# nfc-pn532-old.net
KiCad netlist of a schematic drawn in EAGLE
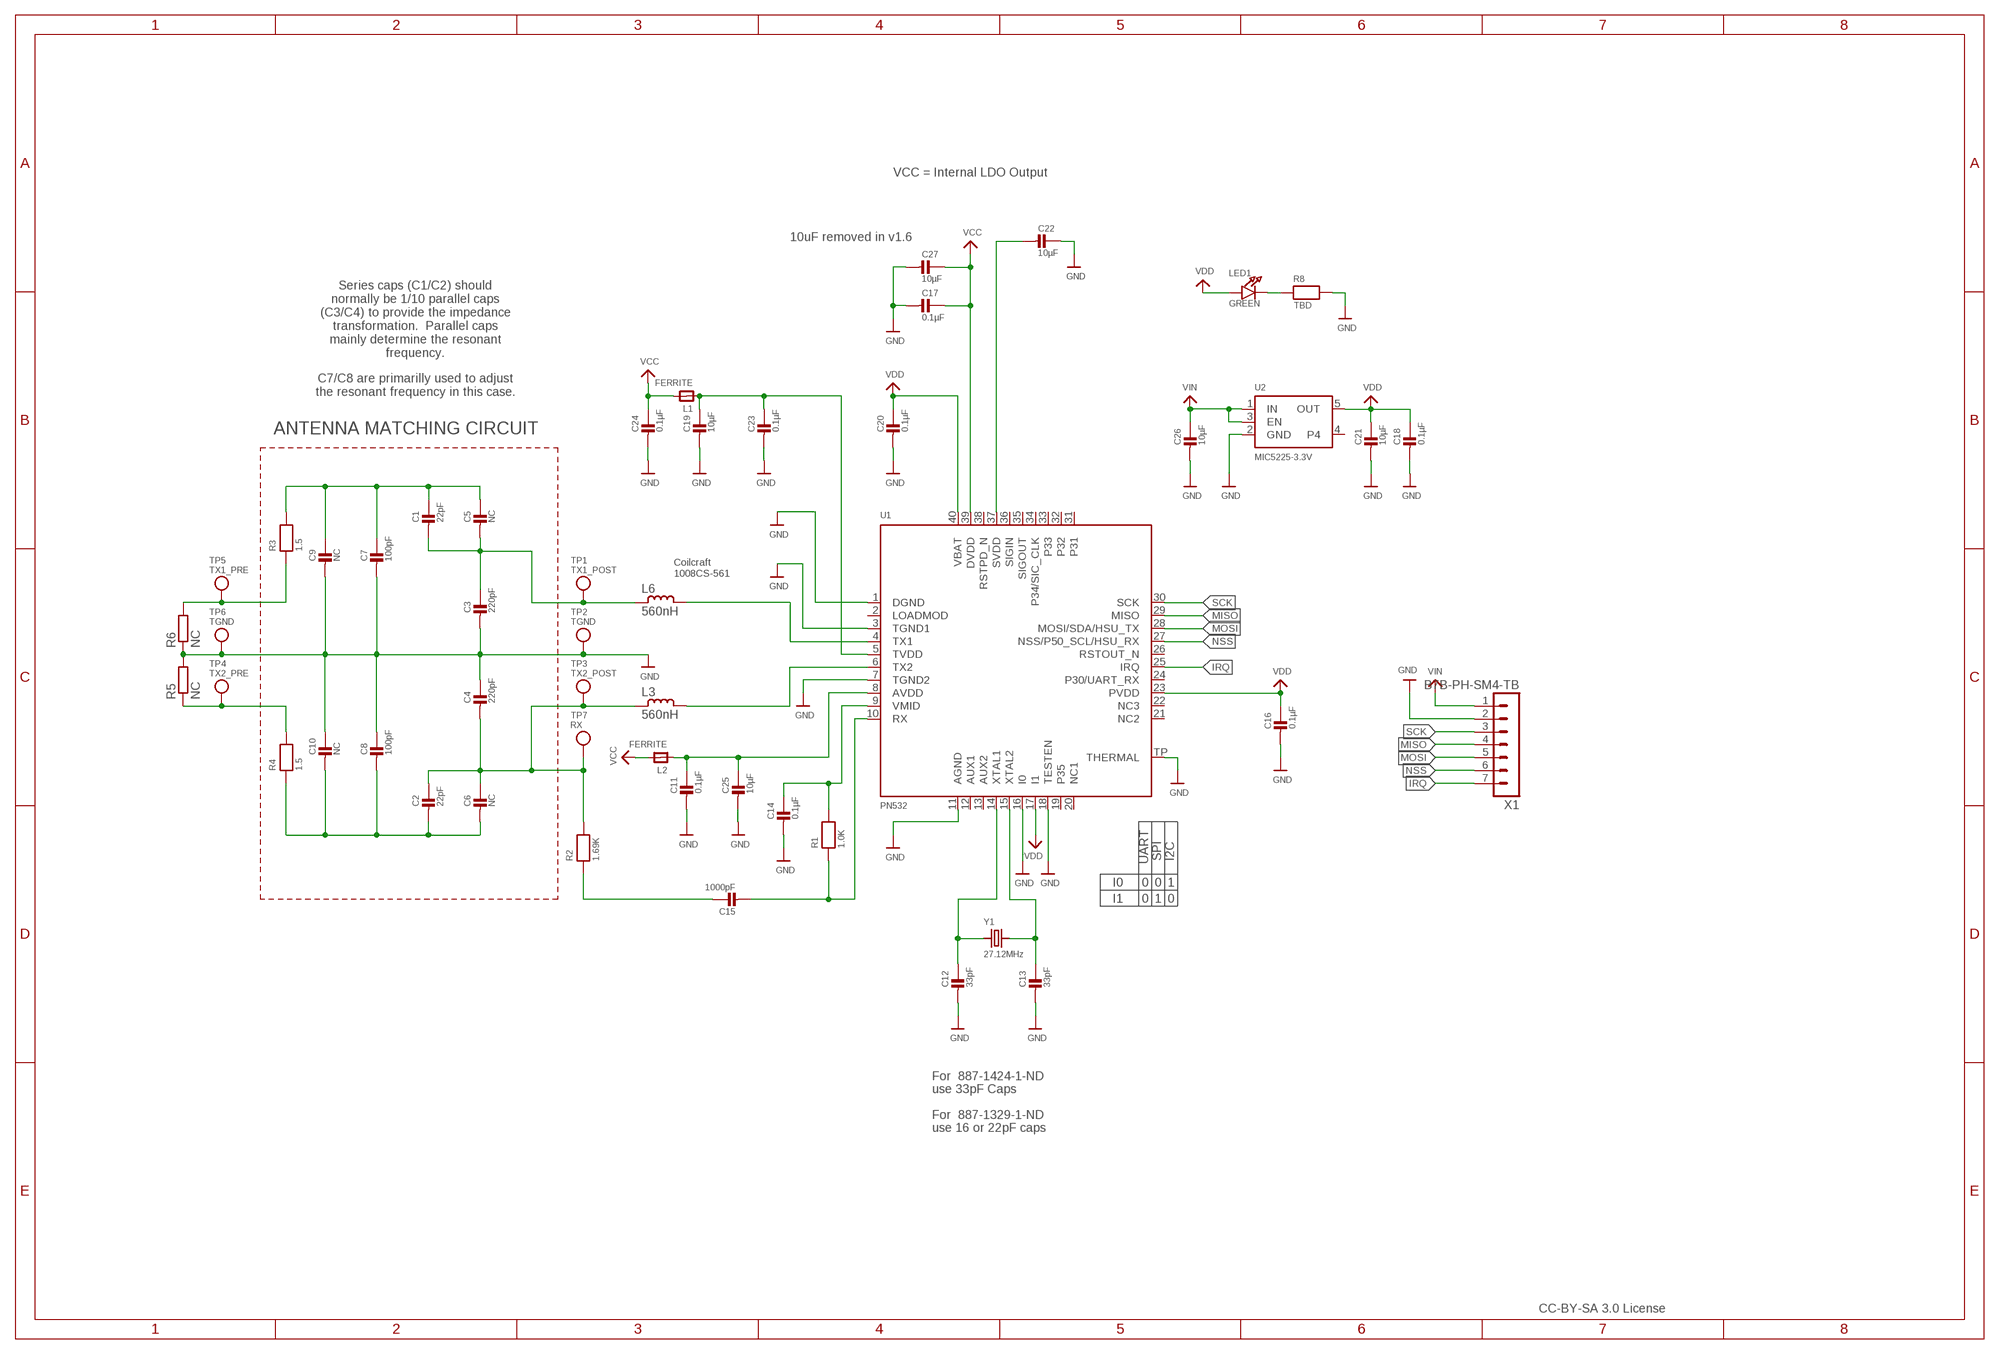
[diagram p0: schematic, sheet 1]

(export (version "E")
  (design (tool "Eeschema 10.0.6"))
  (components
    (comp (ref "C1")
      (value "22pF")
      (footprint "eagle-import:0805-NO")
      (libsource (lib "eagle-import") (part "CAP_CERAMIC0805-NOOUTLINE"))
    )
    (comp (ref "C2")
      (value "22pF")
      (footprint "eagle-import:0805-NO")
      (libsource (lib "eagle-import") (part "CAP_CERAMIC0805-NOOUTLINE"))
    )
    (comp (ref "C3")
      (value "220pF")
      (footprint "eagle-import:0805-NO")
      (libsource (lib "eagle-import") (part "CAP_CERAMIC0805-NOOUTLINE"))
    )
    (comp (ref "C4")
      (value "220pF")
      (footprint "eagle-import:0805-NO")
      (libsource (lib "eagle-import") (part "CAP_CERAMIC0805-NOOUTLINE"))
    )
    (comp (ref "C5")
      (value "NC")
      (footprint "eagle-import:0805-NO")
      (libsource (lib "eagle-import") (part "CAP_CERAMIC0805-NOOUTLINE"))
    )
    (comp (ref "C6")
      (value "NC")
      (footprint "eagle-import:0805-NO")
      (libsource (lib "eagle-import") (part "CAP_CERAMIC0805-NOOUTLINE"))
    )
    (comp (ref "C7")
      (value "100pF")
      (footprint "eagle-import:0805-NO")
      (libsource (lib "eagle-import") (part "CAP_CERAMIC0805-NOOUTLINE"))
    )
    (comp (ref "C8")
      (value "100pF")
      (footprint "eagle-import:0805-NO")
      (libsource (lib "eagle-import") (part "CAP_CERAMIC0805-NOOUTLINE"))
    )
    (comp (ref "C9")
      (value "NC")
      (footprint "eagle-import:0805-NO")
      (libsource (lib "eagle-import") (part "CAP_CERAMIC0805-NOOUTLINE"))
    )
    (comp (ref "C10")
      (value "NC")
      (footprint "eagle-import:0805-NO")
      (libsource (lib "eagle-import") (part "CAP_CERAMIC0805-NOOUTLINE"))
    )
    (comp (ref "C11")
      (value "0.1µF")
      (footprint "eagle-import:0805-NO")
      (libsource (lib "eagle-import") (part "CAP_CERAMIC0805-NOOUTLINE"))
    )
    (comp (ref "C12")
      (value "33pF")
      (footprint "eagle-import:0805-NO")
      (libsource (lib "eagle-import") (part "CAP_CERAMIC0805-NOOUTLINE"))
    )
    (comp (ref "C13")
      (value "33pF")
      (footprint "eagle-import:0805-NO")
      (libsource (lib "eagle-import") (part "CAP_CERAMIC0805-NOOUTLINE"))
    )
    (comp (ref "C14")
      (value "0.1µF")
      (footprint "eagle-import:0805-NO")
      (libsource (lib "eagle-import") (part "CAP_CERAMIC0805-NOOUTLINE"))
    )
    (comp (ref "C15")
      (value "1000pF")
      (footprint "eagle-import:0805-NO")
      (libsource (lib "eagle-import") (part "CAP_CERAMIC0805-NOOUTLINE"))
    )
    (comp (ref "C16")
      (value "0.1µF")
      (footprint "eagle-import:0805-NO")
      (libsource (lib "eagle-import") (part "CAP_CERAMIC0805-NOOUTLINE"))
    )
    (comp (ref "C17")
      (value "0.1µF")
      (footprint "eagle-import:0805-NO")
      (libsource (lib "eagle-import") (part "CAP_CERAMIC0805-NOOUTLINE"))
    )
    (comp (ref "C18")
      (value "0.1µF")
      (footprint "eagle-import:0805-NO")
      (libsource (lib "eagle-import") (part "CAP_CERAMIC0805-NOOUTLINE"))
    )
    (comp (ref "C19")
      (value "10µF")
      (footprint "eagle-import:0805-NO")
      (libsource (lib "eagle-import") (part "CAP_CERAMIC0805-NOOUTLINE"))
    )
    (comp (ref "C20")
      (value "0.1µF")
      (footprint "eagle-import:0805-NO")
      (libsource (lib "eagle-import") (part "CAP_CERAMIC0805-NOOUTLINE"))
    )
    (comp (ref "C21")
      (value "10µF")
      (footprint "eagle-import:0805-NO")
      (libsource (lib "eagle-import") (part "CAP_CERAMIC0805-NOOUTLINE"))
    )
    (comp (ref "C22")
      (value "10µF")
      (footprint "eagle-import:0805-NO")
      (libsource (lib "eagle-import") (part "CAP_CERAMIC0805-NOOUTLINE"))
    )
    (comp (ref "C23")
      (value "0.1µF")
      (footprint "eagle-import:0805-NO")
      (libsource (lib "eagle-import") (part "CAP_CERAMIC0805-NOOUTLINE"))
    )
    (comp (ref "C24")
      (value "0.1µF")
      (footprint "eagle-import:0805-NO")
      (libsource (lib "eagle-import") (part "CAP_CERAMIC0805-NOOUTLINE"))
    )
    (comp (ref "C25")
      (value "10µF")
      (footprint "eagle-import:0805-NO")
      (libsource (lib "eagle-import") (part "CAP_CERAMIC0805-NOOUTLINE"))
    )
    (comp (ref "C26")
      (value "10µF")
      (footprint "eagle-import:0805-NO")
      (libsource (lib "eagle-import") (part "CAP_CERAMIC0805-NOOUTLINE"))
    )
    (comp (ref "C27")
      (value "10µF")
      (footprint "eagle-import:0805-NO")
      (libsource (lib "eagle-import") (part "CAP_CERAMIC0805-NOOUTLINE"))
    )
    (comp (ref "L1")
      (value "FERRITE")
      (footprint "eagle-import:0805")
      (libsource (lib "eagle-import") (part "FERRITE0805"))
    )
    (comp (ref "L2")
      (value "FERRITE")
      (footprint "eagle-import:0805")
      (libsource (lib "eagle-import") (part "FERRITE0805"))
    )
    (comp (ref "L3")
      (value "560nH")
      (footprint "eagle-import:L1008CS")
      (libsource (lib "eagle-import") (part "L-1008CS"))
    )
    (comp (ref "L6")
      (value "560nH")
      (footprint "eagle-import:L1008CS")
      (libsource (lib "eagle-import") (part "L-1008CS"))
    )
    (comp (ref "LED1")
      (value "GREEN")
      (footprint "eagle-import:CHIPLED_0805_NOOUTLINE")
      (libsource (lib "eagle-import") (part "LED0805_NOOUTLINE"))
    )
    (comp (ref "R1")
      (value "1.0K")
      (footprint "eagle-import:0805-NO")
      (libsource (lib "eagle-import") (part "RESISTOR0805_NOOUTLINE"))
    )
    (comp (ref "R2")
      (value "1.69K")
      (footprint "eagle-import:0805-NO")
      (libsource (lib "eagle-import") (part "RESISTOR0805_NOOUTLINE"))
    )
    (comp (ref "R3")
      (value "1.5")
      (footprint "eagle-import:0805-NO")
      (libsource (lib "eagle-import") (part "RESISTOR0805_NOOUTLINE"))
    )
    (comp (ref "R4")
      (value "1.5")
      (footprint "eagle-import:0805-NO")
      (libsource (lib "eagle-import") (part "RESISTOR0805_NOOUTLINE"))
    )
    (comp (ref "R5")
      (value "NC")
      (footprint "eagle-import:R0201")
      (libsource (lib "eagle-import") (part "R-EU_R0201"))
    )
    (comp (ref "R6")
      (value "NC")
      (footprint "eagle-import:R0201")
      (libsource (lib "eagle-import") (part "R-EU_R0201"))
    )
    (comp (ref "R8")
      (value "TBD")
      (footprint "eagle-import:0805-NO")
      (libsource (lib "eagle-import") (part "RESISTOR0805_NOOUTLINE"))
    )
    (comp (ref "TP1")
      (value "TX1_POST")
      (footprint "eagle-import:TESTPOINT_ROUND_1MM")
      (libsource (lib "eagle-import") (part "TESTPOINTROUND1MM"))
    )
    (comp (ref "TP2")
      (value "TGND")
      (footprint "eagle-import:TESTPOINT_ROUND_1MM")
      (libsource (lib "eagle-import") (part "TESTPOINTROUND1MM"))
    )
    (comp (ref "TP3")
      (value "TX2_POST")
      (footprint "eagle-import:TESTPOINT_ROUND_1MM")
      (libsource (lib "eagle-import") (part "TESTPOINTROUND1MM"))
    )
    (comp (ref "TP4")
      (value "TX2_PRE")
      (footprint "eagle-import:TESTPOINT_ROUND_1MM")
      (libsource (lib "eagle-import") (part "TESTPOINTROUND1MM"))
    )
    (comp (ref "TP5")
      (value "TX1_PRE")
      (footprint "eagle-import:TESTPOINT_ROUND_1MM")
      (libsource (lib "eagle-import") (part "TESTPOINTROUND1MM"))
    )
    (comp (ref "TP6")
      (value "TGND")
      (footprint "eagle-import:TESTPOINT_ROUND_1MM")
      (libsource (lib "eagle-import") (part "TESTPOINTROUND1MM"))
    )
    (comp (ref "TP7")
      (value "RX")
      (footprint "eagle-import:TESTPOINT_ROUND_1MM")
      (libsource (lib "eagle-import") (part "TESTPOINTROUND1MM"))
    )
    (comp (ref "U1")
      (value "PN532")
      (footprint "eagle-import:HVQFN40-6X6")
      (libsource (lib "eagle-import") (part "PN532"))
    )
    (comp (ref "U2")
      (value "MIC5225-3.3V")
      (footprint "eagle-import:SOT23-5")
      (libsource (lib "eagle-import") (part "VREG_SOT23-5"))
    )
    (comp (ref "X1")
      (value "B7B-PH-SM4-TB")
      (footprint "eagle-import:B7B-PH-SM4-TB")
      (libsource (lib "eagle-import") (part "B7B-PH-SM4-TB"))
    )
    (comp (ref "Y1")
      (value "27.12MHz")
      (footprint "eagle-import:CRYSTAL_3.2X2.5")
      (libsource (lib "eagle-import") (part "CRYSTAL3.2X2.5"))
    )
  )
  (nets
    (net (code "1") (name "GND") (class "Default")
      (node (ref "C10") (pin "1") (pinfunction "1_1") (pintype "passive"))
      (node (ref "C11") (pin "2") (pinfunction "2_2") (pintype "passive"))
      (node (ref "C12") (pin "2") (pinfunction "2_2") (pintype "passive"))
      (node (ref "C13") (pin "2") (pinfunction "2_2") (pintype "passive"))
      (node (ref "C14") (pin "2") (pinfunction "2_2") (pintype "passive"))
      (node (ref "C16") (pin "2") (pinfunction "2_2") (pintype "passive"))
      (node (ref "C17") (pin "2") (pinfunction "2_2") (pintype "passive"))
      (node (ref "C18") (pin "2") (pinfunction "2_2") (pintype "passive"))
      (node (ref "C19") (pin "2") (pinfunction "2_2") (pintype "passive"))
      (node (ref "C20") (pin "2") (pinfunction "2_2") (pintype "passive"))
      (node (ref "C21") (pin "2") (pinfunction "2_2") (pintype "passive"))
      (node (ref "C22") (pin "1") (pinfunction "1_1") (pintype "passive"))
      (node (ref "C23") (pin "2") (pinfunction "2_2") (pintype "passive"))
      (node (ref "C24") (pin "2") (pinfunction "2_2") (pintype "passive"))
      (node (ref "C25") (pin "2") (pinfunction "2_2") (pintype "passive"))
      (node (ref "C26") (pin "2") (pinfunction "2_2") (pintype "passive"))
      (node (ref "C27") (pin "2") (pinfunction "2_2") (pintype "passive"))
      (node (ref "C3") (pin "2") (pinfunction "2_2") (pintype "passive"))
      (node (ref "C4") (pin "1") (pinfunction "1_1") (pintype "passive"))
      (node (ref "C7") (pin "2") (pinfunction "2_2") (pintype "passive"))
      (node (ref "C8") (pin "1") (pinfunction "1_1") (pintype "passive"))
      (node (ref "C9") (pin "2") (pinfunction "2_2") (pintype "passive"))
      (node (ref "R5") (pin "2") (pinfunction "2_2") (pintype "passive"))
      (node (ref "R6") (pin "1") (pinfunction "1_1") (pintype "passive"))
      (node (ref "R8") (pin "2") (pinfunction "2_2") (pintype "passive"))
      (node (ref "TP2") (pin "P$1") (pinfunction "P$1_P$1") (pintype "bidirectional"))
      (node (ref "TP6") (pin "P$1") (pinfunction "P$1_P$1") (pintype "bidirectional"))
      (node (ref "U1") (pin "1") (pinfunction "DGND_1") (pintype "bidirectional"))
      (node (ref "U1") (pin "11") (pinfunction "AGND_11") (pintype "bidirectional"))
      (node (ref "U1") (pin "16") (pinfunction "I0_16") (pintype "bidirectional"))
      (node (ref "U1") (pin "18") (pinfunction "TESTEN_18") (pintype "bidirectional"))
      (node (ref "U1") (pin "3") (pinfunction "TGND1_3") (pintype "bidirectional"))
      (node (ref "U1") (pin "7") (pinfunction "TGND2_7") (pintype "bidirectional"))
      (node (ref "U1") (pin "TP") (pinfunction "THERMAL_TP") (pintype "bidirectional"))
      (node (ref "U2") (pin "2") (pinfunction "GND_2") (pintype "power_in"))
      (node (ref "X1") (pin "2") (pinfunction "2_2") (pintype "passive"))
    )
    (net (code "2") (name "IRQ") (class "Default")
      (node (ref "U1") (pin "25") (pinfunction "IRQ_25") (pintype "bidirectional"))
      (node (ref "X1") (pin "7") (pinfunction "7_7") (pintype "passive"))
    )
    (net (code "3") (name "MISO") (class "Default")
      (node (ref "U1") (pin "29") (pinfunction "MISO_29") (pintype "bidirectional"))
      (node (ref "X1") (pin "4") (pinfunction "4_4") (pintype "passive"))
    )
    (net (code "4") (name "MOSI") (class "Default")
      (node (ref "U1") (pin "28") (pinfunction "MOSI/SDA/HSU_TX_28") (pintype "bidirectional"))
      (node (ref "X1") (pin "5") (pinfunction "5_5") (pintype "passive"))
    )
    (net (code "5") (name "NSS") (class "Default")
      (node (ref "U1") (pin "27") (pinfunction "NSS/P50_SCL/HSU_RX_27") (pintype "bidirectional"))
      (node (ref "X1") (pin "6") (pinfunction "6_6") (pintype "passive"))
    )
    (net (code "6") (name "Net-(C1-Pad1)") (class "Default")
      (node (ref "C1") (pin "1") (pinfunction "1_1") (pintype "passive"))
      (node (ref "C5") (pin "1") (pinfunction "1_1") (pintype "passive"))
      (node (ref "C7") (pin "1") (pinfunction "1_1") (pintype "passive"))
      (node (ref "C9") (pin "1") (pinfunction "1_1") (pintype "passive"))
      (node (ref "R3") (pin "2") (pinfunction "2_2") (pintype "passive"))
    )
    (net (code "7") (name "Net-(C10-Pad2)") (class "Default")
      (node (ref "C10") (pin "2") (pinfunction "2_2") (pintype "passive"))
      (node (ref "C2") (pin "2") (pinfunction "2_2") (pintype "passive"))
      (node (ref "C6") (pin "2") (pinfunction "2_2") (pintype "passive"))
      (node (ref "C8") (pin "2") (pinfunction "2_2") (pintype "passive"))
      (node (ref "R4") (pin "1") (pinfunction "1_1") (pintype "passive"))
    )
    (net (code "8") (name "Net-(C15-Pad1)") (class "Default")
      (node (ref "C15") (pin "1") (pinfunction "1_1") (pintype "passive"))
      (node (ref "R2") (pin "1") (pinfunction "1_1") (pintype "passive"))
    )
    (net (code "9") (name "Net-(L1-P$1)") (class "Default")
      (node (ref "C19") (pin "1") (pinfunction "1_1") (pintype "passive"))
      (node (ref "C23") (pin "1") (pinfunction "1_1") (pintype "passive"))
      (node (ref "L1") (pin "1") (pinfunction "P$1_1") (pintype "passive"))
      (node (ref "U1") (pin "5") (pinfunction "TVDD_5") (pintype "bidirectional"))
    )
    (net (code "10") (name "Net-(L2-P$1)") (class "Default")
      (node (ref "C11") (pin "1") (pinfunction "1_1") (pintype "passive"))
      (node (ref "C25") (pin "1") (pinfunction "1_1") (pintype "passive"))
      (node (ref "L2") (pin "1") (pinfunction "P$1_1") (pintype "passive"))
      (node (ref "U1") (pin "8") (pinfunction "AVDD_8") (pintype "bidirectional"))
    )
    (net (code "11") (name "Net-(L3-P$1)") (class "Default")
      (node (ref "C2") (pin "1") (pinfunction "1_1") (pintype "passive"))
      (node (ref "C4") (pin "2") (pinfunction "2_2") (pintype "passive"))
      (node (ref "C6") (pin "1") (pinfunction "1_1") (pintype "passive"))
      (node (ref "L3") (pin "1") (pinfunction "P$1_1") (pintype "passive"))
      (node (ref "R2") (pin "2") (pinfunction "2_2") (pintype "passive"))
      (node (ref "TP3") (pin "P$1") (pinfunction "P$1_P$1") (pintype "bidirectional"))
      (node (ref "TP7") (pin "P$1") (pinfunction "P$1_P$1") (pintype "bidirectional"))
    )
    (net (code "12") (name "Net-(L3-P$2)") (class "Default")
      (node (ref "L3") (pin "2") (pinfunction "P$2_2") (pintype "passive"))
      (node (ref "U1") (pin "6") (pinfunction "TX2_6") (pintype "bidirectional"))
    )
    (net (code "13") (name "Net-(L6-P$1)") (class "Default")
      (node (ref "C1") (pin "2") (pinfunction "2_2") (pintype "passive"))
      (node (ref "C3") (pin "1") (pinfunction "1_1") (pintype "passive"))
      (node (ref "C5") (pin "2") (pinfunction "2_2") (pintype "passive"))
      (node (ref "L6") (pin "1") (pinfunction "P$1_1") (pintype "passive"))
      (node (ref "TP1") (pin "P$1") (pinfunction "P$1_P$1") (pintype "bidirectional"))
    )
    (net (code "14") (name "Net-(L6-P$2)") (class "Default")
      (node (ref "L6") (pin "2") (pinfunction "P$2_2") (pintype "passive"))
      (node (ref "U1") (pin "4") (pinfunction "TX1_4") (pintype "bidirectional"))
    )
    (net (code "15") (name "Net-(LED1-PadC)") (class "Default")
      (node (ref "LED1") (pin "C") (pinfunction "C_C") (pintype "passive"))
      (node (ref "R8") (pin "1") (pinfunction "1_1") (pintype "passive"))
    )
    (net (code "16") (name "Net-(R3-Pad1)") (class "Default")
      (node (ref "R3") (pin "1") (pinfunction "1_1") (pintype "passive"))
      (node (ref "R6") (pin "2") (pinfunction "2_2") (pintype "passive"))
      (node (ref "TP5") (pin "P$1") (pinfunction "P$1_P$1") (pintype "bidirectional"))
    )
    (net (code "17") (name "Net-(R4-Pad2)") (class "Default")
      (node (ref "R4") (pin "2") (pinfunction "2_2") (pintype "passive"))
      (node (ref "R5") (pin "1") (pinfunction "1_1") (pintype "passive"))
      (node (ref "TP4") (pin "P$1") (pinfunction "P$1_P$1") (pintype "bidirectional"))
    )
    (net (code "18") (name "Net-(U1-RX)") (class "Default")
      (node (ref "C15") (pin "2") (pinfunction "2_2") (pintype "passive"))
      (node (ref "R1") (pin "1") (pinfunction "1_1") (pintype "passive"))
      (node (ref "U1") (pin "10") (pinfunction "RX_10") (pintype "bidirectional"))
    )
    (net (code "19") (name "Net-(U1-SVDD)") (class "Default")
      (node (ref "C22") (pin "2") (pinfunction "2_2") (pintype "passive"))
      (node (ref "U1") (pin "37") (pinfunction "SVDD_37") (pintype "bidirectional"))
    )
    (net (code "20") (name "Net-(U1-VMID)") (class "Default")
      (node (ref "C14") (pin "1") (pinfunction "1_1") (pintype "passive"))
      (node (ref "R1") (pin "2") (pinfunction "2_2") (pintype "passive"))
      (node (ref "U1") (pin "9") (pinfunction "VMID_9") (pintype "bidirectional"))
    )
    (net (code "21") (name "Net-(U1-XTAL1)") (class "Default")
      (node (ref "C12") (pin "1") (pinfunction "1_1") (pintype "passive"))
      (node (ref "U1") (pin "14") (pinfunction "XTAL1_14") (pintype "bidirectional"))
      (node (ref "Y1") (pin "1") (pinfunction "1_1") (pintype "passive"))
    )
    (net (code "22") (name "Net-(U1-XTAL2)") (class "Default")
      (node (ref "C13") (pin "1") (pinfunction "1_1") (pintype "passive"))
      (node (ref "U1") (pin "15") (pinfunction "XTAL2_15") (pintype "bidirectional"))
      (node (ref "Y1") (pin "2") (pinfunction "2_2") (pintype "passive"))
    )
    (net (code "23") (name "SCK") (class "Default")
      (node (ref "U1") (pin "30") (pinfunction "SCK_30") (pintype "bidirectional"))
      (node (ref "X1") (pin "3") (pinfunction "3_3") (pintype "passive"))
    )
    (net (code "24") (name "VCC") (class "Default")
      (node (ref "C17") (pin "1") (pinfunction "1_1") (pintype "passive"))
      (node (ref "C24") (pin "1") (pinfunction "1_1") (pintype "passive"))
      (node (ref "C27") (pin "1") (pinfunction "1_1") (pintype "passive"))
      (node (ref "L1") (pin "2") (pinfunction "P$2_2") (pintype "passive"))
      (node (ref "L2") (pin "2") (pinfunction "P$2_2") (pintype "passive"))
      (node (ref "U1") (pin "39") (pinfunction "DVDD_39") (pintype "bidirectional"))
    )
    (net (code "25") (name "VDD") (class "Default")
      (node (ref "C16") (pin "1") (pinfunction "1_1") (pintype "passive"))
      (node (ref "C18") (pin "1") (pinfunction "1_1") (pintype "passive"))
      (node (ref "C20") (pin "1") (pinfunction "1_1") (pintype "passive"))
      (node (ref "C21") (pin "1") (pinfunction "1_1") (pintype "passive"))
      (node (ref "LED1") (pin "A") (pinfunction "A_A") (pintype "passive"))
      (node (ref "U1") (pin "17") (pinfunction "I1_17") (pintype "bidirectional"))
      (node (ref "U1") (pin "23") (pinfunction "PVDD_23") (pintype "bidirectional"))
      (node (ref "U1") (pin "40") (pinfunction "VBAT_40") (pintype "bidirectional"))
      (node (ref "U2") (pin "5") (pinfunction "OUT_5") (pintype "power_in"))
    )
    (net (code "26") (name "VIN") (class "Default")
      (node (ref "C26") (pin "1") (pinfunction "1_1") (pintype "passive"))
      (node (ref "U2") (pin "1") (pinfunction "IN_1") (pintype "power_in"))
      (node (ref "U2") (pin "3") (pinfunction "EN_3") (pintype "input"))
      (node (ref "X1") (pin "1") (pinfunction "1_1") (pintype "passive"))
    )
    (net (code "27") (name "unconnected-(U1-AUX1-Pad12)") (class "Default")
      (node (ref "U1") (pin "12") (pinfunction "AUX1_12") (pintype "bidirectional"))
    )
    (net (code "28") (name "unconnected-(U1-AUX2-Pad13)") (class "Default")
      (node (ref "U1") (pin "13") (pinfunction "AUX2_13") (pintype "bidirectional"))
    )
    (net (code "29") (name "unconnected-(U1-LOADMOD-Pad2)") (class "Default")
      (node (ref "U1") (pin "2") (pinfunction "LOADMOD_2") (pintype "bidirectional"))
    )
    (net (code "30") (name "unconnected-(U1-NC1-Pad20)") (class "Default")
      (node (ref "U1") (pin "20") (pinfunction "NC1_20") (pintype "bidirectional"))
    )
    (net (code "31") (name "unconnected-(U1-NC2-Pad21)") (class "Default")
      (node (ref "U1") (pin "21") (pinfunction "NC2_21") (pintype "bidirectional"))
    )
    (net (code "32") (name "unconnected-(U1-NC3-Pad22)") (class "Default")
      (node (ref "U1") (pin "22") (pinfunction "NC3_22") (pintype "bidirectional"))
    )
    (net (code "33") (name "unconnected-(U1-P30{slash}UART_RX-Pad24)") (class "Default")
      (node (ref "U1") (pin "24") (pinfunction "P30/UART_RX_24") (pintype "bidirectional"))
    )
    (net (code "34") (name "unconnected-(U1-P31-Pad31)") (class "Default")
      (node (ref "U1") (pin "31") (pinfunction "P31_31") (pintype "bidirectional"))
    )
    (net (code "35") (name "unconnected-(U1-P32-Pad32)") (class "Default")
      (node (ref "U1") (pin "32") (pinfunction "P32_32") (pintype "bidirectional"))
    )
    (net (code "36") (name "unconnected-(U1-P33-Pad33)") (class "Default")
      (node (ref "U1") (pin "33") (pinfunction "P33_33") (pintype "bidirectional"))
    )
    (net (code "37") (name "unconnected-(U1-P34{slash}SIC_CLK-Pad34)") (class "Default")
      (node (ref "U1") (pin "34") (pinfunction "P34/SIC_CLK_34") (pintype "bidirectional"))
    )
    (net (code "38") (name "unconnected-(U1-P35-Pad19)") (class "Default")
      (node (ref "U1") (pin "19") (pinfunction "P35_19") (pintype "bidirectional"))
    )
    (net (code "39") (name "unconnected-(U1-RSTOUT_N-Pad26)") (class "Default")
      (node (ref "U1") (pin "26") (pinfunction "RSTOUT_N_26") (pintype "bidirectional"))
    )
    (net (code "40") (name "unconnected-(U1-RSTPD_N-Pad38)") (class "Default")
      (node (ref "U1") (pin "38") (pinfunction "RSTPD_N_38") (pintype "bidirectional"))
    )
    (net (code "41") (name "unconnected-(U1-SIGIN-Pad36)") (class "Default")
      (node (ref "U1") (pin "36") (pinfunction "SIGIN_36") (pintype "bidirectional"))
    )
    (net (code "42") (name "unconnected-(U1-SIGOUT-Pad35)") (class "Default")
      (node (ref "U1") (pin "35") (pinfunction "SIGOUT_35") (pintype "bidirectional"))
    )
    (net (code "43") (name "unconnected-(U2-P4-Pad4)") (class "Default")
      (node (ref "U2") (pin "4") (pinfunction "P4_4") (pintype "bidirectional"))
    )
  )
)
